# AudioAmp.net
KiCad netlist of a schematic drawn in Altium Designer
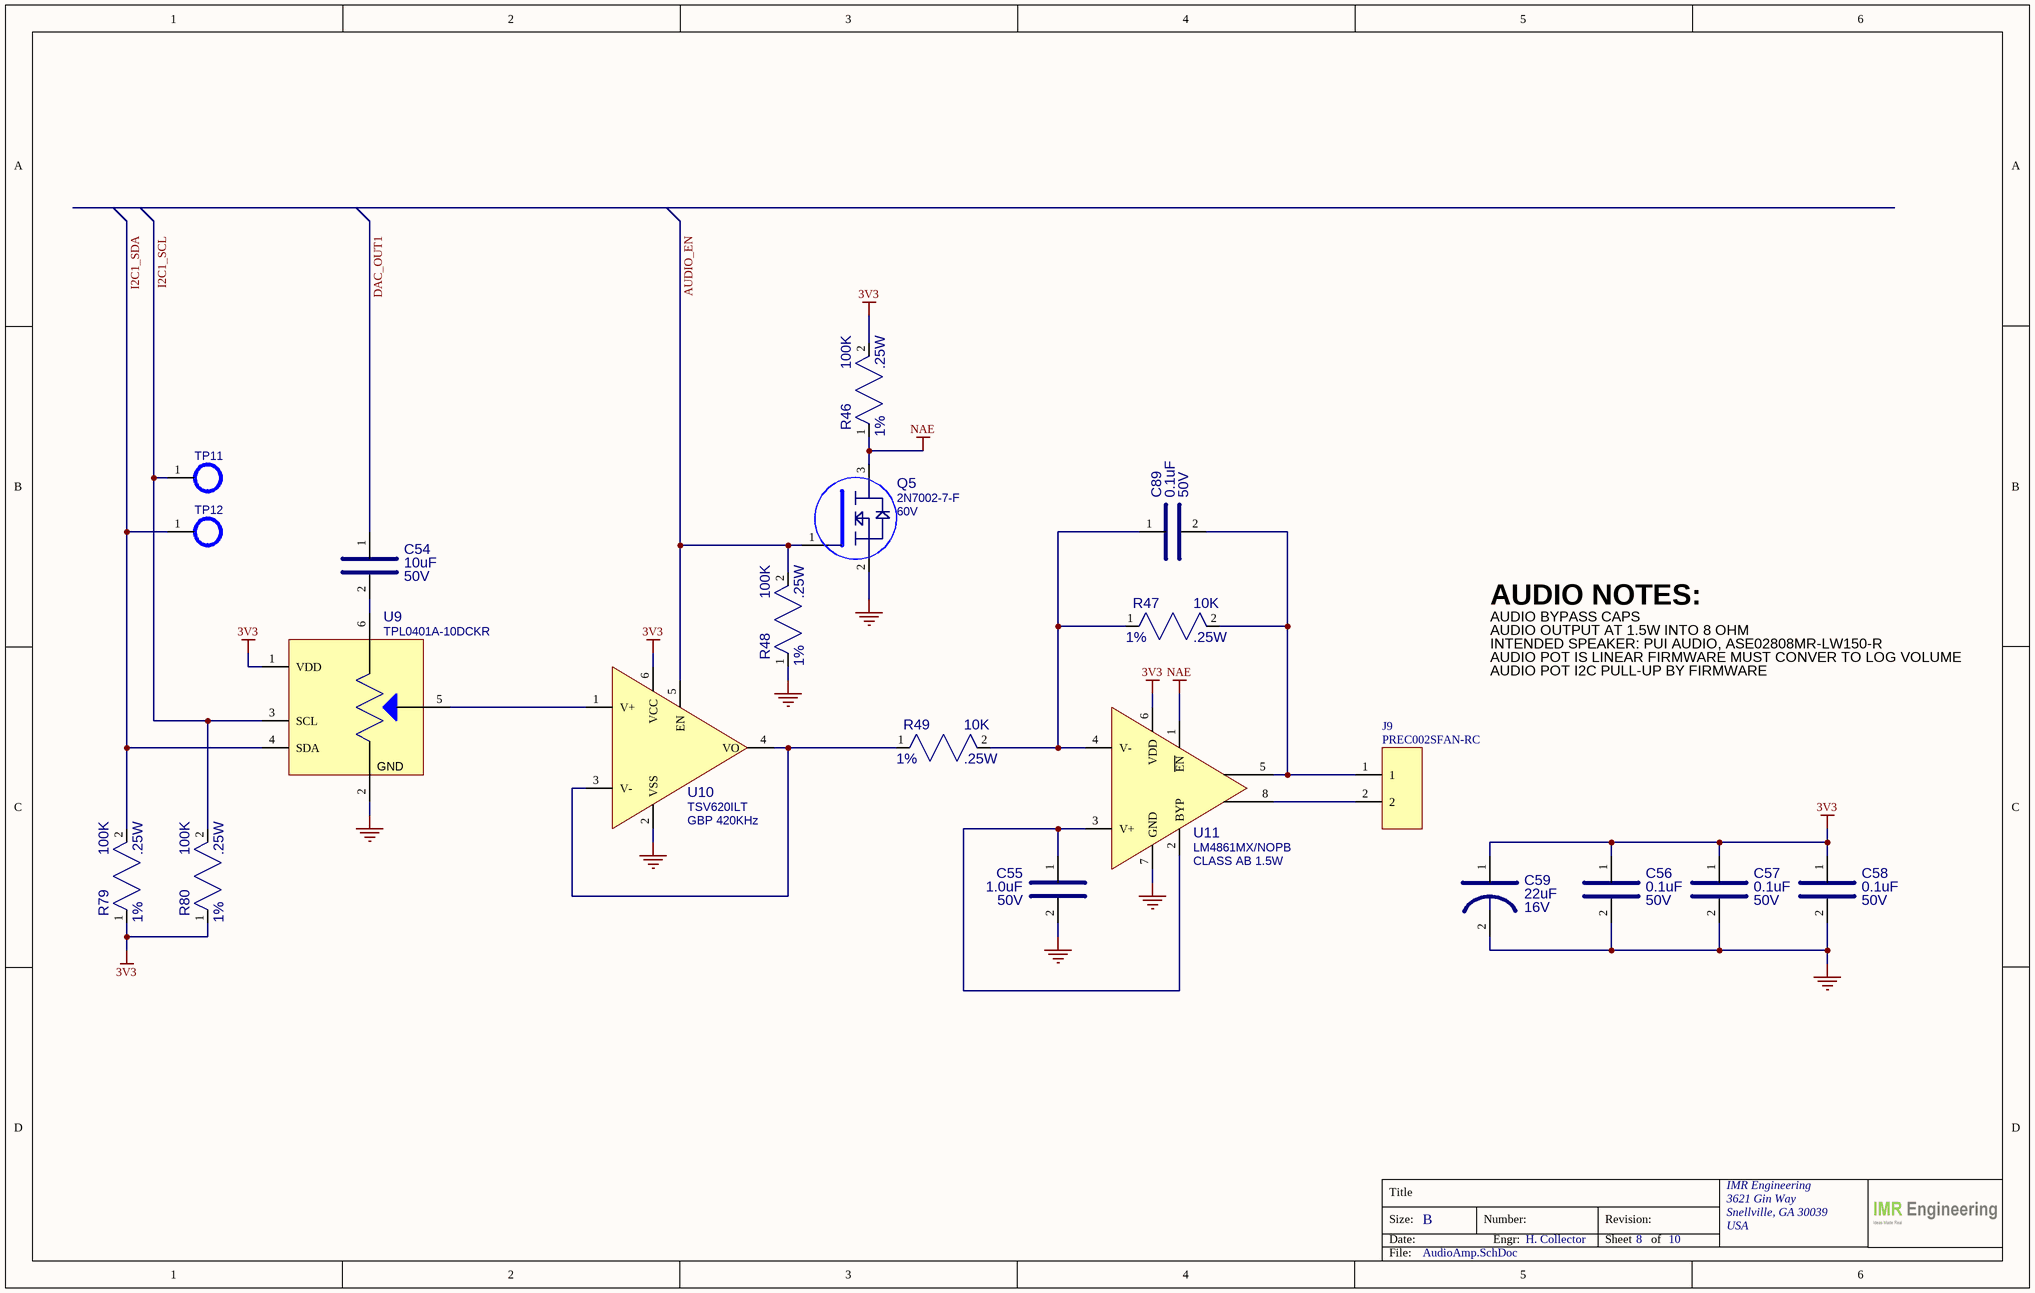
[diagram p0: AudioAmp.SchDoc]

(export (version "E")
  (design (tool "Eeschema 10.0.6"))
  (components
    (comp (ref "C54")
      (value "10uF")
      (footprint "CAP_1206")
      (description "CAP CER 10UF 50V X5R 1206")
      (fields
        (field (name "MFG") "Samsung Electro-Mechanics")
        (field (name "TOLERANCE") "10%")
        (field (name "VOLTAGE") "50V")
      )
      (libsource (lib "IMR_Lib") (part "CAP_10UF_50V_1206"))
    )
    (comp (ref "C55")
      (value "1.0uF")
      (footprint "CAP_0805")
      (description "CAP CER 1UF 50V X7R 0805")
      (fields
        (field (name "MFG") "Taiyo Yuden")
        (field (name "TOLERANCE") "20%")
        (field (name "VOLTAGE") "50V")
      )
      (libsource (lib "IMR_Lib") (part "CAP_1.0UF_50V_0805"))
    )
    (comp (ref "C56")
      (value "0.1uF")
      (footprint "CAP_0805")
      (description "CAP CER 0.1UF 50V X7R 0805")
      (fields (field (name "MFG") "AVX") (field (name "TOLERANCE") "10%") (field (name "VOLTAGE") "50V"))
      (libsource (lib "IMR_Lib") (part "CAP_0.1UF_50V_0805"))
    )
    (comp (ref "C57")
      (value "0.1uF")
      (footprint "CAP_0805")
      (description "CAP CER 0.1UF 50V X7R 0805")
      (fields (field (name "MFG") "AVX") (field (name "TOLERANCE") "10%") (field (name "VOLTAGE") "50V"))
      (libsource (lib "IMR_Lib") (part "CAP_0.1UF_50V_0805"))
    )
    (comp (ref "C58")
      (value "0.1uF")
      (footprint "CAP_0805")
      (description "CAP CER 0.1UF 50V X7R 0805")
      (fields (field (name "MFG") "AVX") (field (name "TOLERANCE") "10%") (field (name "VOLTAGE") "50V"))
      (libsource (lib "IMR_Lib") (part "CAP_0.1UF_50V_0805"))
    )
    (comp (ref "C59")
      (value "22uF")
      (footprint "CAP_2312")
      (description "CAP TANT 22UF 20% 16V 2312")
      (fields
        (field (name "MFG") "AVX Corporation")
        (field (name "TOLERANCE") "10%")
        (field (name "VOLTAGE") "16V")
      )
      (libsource (lib "IMR_Lib") (part "CAP_22UF_16V_TANT"))
    )
    (comp (ref "C89")
      (value "0.1uF")
      (footprint "CAP_0805")
      (description "CAP CER 0.1UF 50V X7R 0805")
      (fields (field (name "MFG") "AVX") (field (name "TOLERANCE") "10%") (field (name "VOLTAGE") "50V"))
      (libsource (lib "IMR_Lib") (part "CAP_0.1UF_50V_0805"))
    )
    (comp (ref "J9")
      (value "PREC002SFAN-RC")
      (footprint "HDR_1X2_100MILL")
      (description "CONN HEADER VERT 2POS 2.54MM")
      (fields (field (name "MFG") "Sullins Connector Solutions"))
      (libsource (lib "IMR_Lib") (part "CONN_2P_SINGLE_ROW"))
    )
    (comp (ref "Q5")
      (value "60V")
      (footprint "SOT-23")
      (description "MOSFET N-CH 60V 115MA SOT23-3")
      (fields
        (field (name "MFG") "Diodes Incorporated")
        (field (name "MFG_PN") "2N7002-7-F")
        (field (name "Comment") "2N7002-7-F")
      )
      (libsource (lib "IMR_Lib") (part "MOSFET_NCH_2N7002-7-F"))
    )
    (comp (ref "R46")
      (value "100K")
      (footprint "PMG_RES_0805")
      (description "RES SMD 100K OHM 1% 1/4W 0805")
      (fields
        (field (name "MFG") "KOA Speer Electronics, Inc.")
        (field (name "TOLERANCE") "1%")
        (field (name "POWER") ".25W")
        (field (name "Comment") "RK73H2ATTD1003F")
      )
      (libsource (lib "IMR_Lib") (part "RES_100K_0805_1/4W_1%"))
    )
    (comp (ref "R47")
      (value "10K")
      (footprint "RES_0805")
      (description "RES SMD 10K OHM 1% 1/4W 0805")
      (fields
        (field (name "MFG") "KOA Speer Electronics, Inc.")
        (field (name "TOLERANCE") "1%")
        (field (name "POWER") ".25W")
        (field (name "Comment") "SG73S2ATTD1002F")
      )
      (libsource (lib "IMR_Lib") (part "RES_10K_0805_1/4W_1%"))
    )
    (comp (ref "R48")
      (value "100K")
      (footprint "PMG_RES_0805")
      (description "RES SMD 100K OHM 1% 1/4W 0805")
      (fields
        (field (name "MFG") "KOA Speer Electronics, Inc.")
        (field (name "TOLERANCE") "1%")
        (field (name "POWER") ".25W")
        (field (name "Comment") "RK73H2ATTD1003F")
      )
      (libsource (lib "IMR_Lib") (part "RES_100K_0805_1/4W_1%"))
    )
    (comp (ref "R49")
      (value "10K")
      (footprint "RES_0805")
      (description "RES SMD 10K OHM 1% 1/4W 0805")
      (fields
        (field (name "MFG") "KOA Speer Electronics, Inc.")
        (field (name "TOLERANCE") "1%")
        (field (name "POWER") ".25W")
        (field (name "Comment") "SG73S2ATTD1002F")
      )
      (libsource (lib "IMR_Lib") (part "RES_10K_0805_1/4W_1%"))
    )
    (comp (ref "R79")
      (value "100K")
      (footprint "PMG_RES_0805")
      (description "RES SMD 100K OHM 1% 1/4W 0805")
      (fields
        (field (name "MFG") "KOA Speer Electronics, Inc.")
        (field (name "TOLERANCE") "1%")
        (field (name "POWER") ".25W")
        (field (name "Comment") "RK73H2ATTD1003F")
      )
      (libsource (lib "IMR_Lib") (part "RES_100K_0805_1/4W_1%"))
    )
    (comp (ref "R80")
      (value "100K")
      (footprint "PMG_RES_0805")
      (description "RES SMD 100K OHM 1% 1/4W 0805")
      (fields
        (field (name "MFG") "KOA Speer Electronics, Inc.")
        (field (name "TOLERANCE") "1%")
        (field (name "POWER") ".25W")
        (field (name "Comment") "RK73H2ATTD1003F")
      )
      (libsource (lib "IMR_Lib") (part "RES_100K_0805_1/4W_1%"))
    )
    (comp (ref "TP11")
      (value "TP_0635MM_HOLE")
      (footprint "TP_0635MM_HOLE")
      (description "3MM IN D. MT HOLE")
      (libsource (lib "IMR_Lib") (part "TP_0635MM_HOLE"))
    )
    (comp (ref "TP12")
      (value "TP_0635MM_HOLE")
      (footprint "TP_0635MM_HOLE")
      (description "3MM IN D. MT HOLE")
      (libsource (lib "IMR_Lib") (part "TP_0635MM_HOLE"))
    )
    (comp (ref "U9")
      (value "10K")
      (footprint "SOT-363_6-TSSOP_SC-88")
      (description "IC DGTL POT 10KOHM 128TAP SC70-6")
      (fields
        (field (name "MFG") "Texas Instruments")
        (field (name "MFG_PN") "TPL0401A-10DCKR")
        (field (name "TOLERANCE") "20%")
        (field (name "POWER") "5.5V")
        (field (name "Comment") "TPL0401A-10DCKR")
      )
      (libsource (lib "IMR_Lib") (part "IC_TPL0401A-10DCKR"))
    )
    (comp (ref "U10")
      (value "GBP 420KHz")
      (footprint "SOT23-6")
      (description "IC OPAMP GP 1 CIRCUIT SOT23-6")
      (fields
        (field (name "MFG") "STMicroelectronics")
        (field (name "MFG_PN") "TSV620ILT")
        (field (name "Comment") "TSV620ILT")
      )
      (libsource (lib "IMR_Lib") (part "IC_OPAMP_TSV620ILT"))
    )
    (comp (ref "U11")
      (value "CLASS AB 1.5W")
      (footprint "SO-8")
      (description "IC AMP CLASS AB MONO 1.5W 8SOIC")
      (fields
        (field (name "MFG") "Texas Instruments")
        (field (name "MFG_PN") "LM4861MX/NOPB")
        (field (name "Comment") "LM4861MX/NOPB")
      )
      (libsource (lib "IMR_Lib") (part "IC_OPAMP_LM4861"))
    )
  )
  (nets
    (net (code "1") (name "/AUDIO_EN") (class "Default")
      (node (ref "Q5") (pin "1") (pinfunction "B_1") (pintype "passive"))
      (node (ref "R48") (pin "2") (pinfunction "2_2") (pintype "passive"))
      (node (ref "U10") (pin "5") (pinfunction "EN_5") (pintype "passive"))
    )
    (net (code "2") (name "/DAC_OUT1") (class "Default")
      (node (ref "C54") (pin "1") (pinfunction "1_1") (pintype "passive"))
    )
    (net (code "3") (name "/I2C1_SCL") (class "Default")
      (node (ref "R80") (pin "2") (pinfunction "2_2") (pintype "passive"))
      (node (ref "TP11") (pin "1") (pinfunction "1_1") (pintype "passive"))
      (node (ref "U9") (pin "3") (pinfunction "SCL_3") (pintype "passive"))
    )
    (net (code "4") (name "/I2C1_SDA") (class "Default")
      (node (ref "R79") (pin "2") (pinfunction "2_2") (pintype "passive"))
      (node (ref "TP12") (pin "1") (pinfunction "1_1") (pintype "passive"))
      (node (ref "U9") (pin "4") (pinfunction "SDA_4") (pintype "passive"))
    )
    (net (code "5") (name "3V3") (class "Default")
      (node (ref "C56") (pin "1") (pinfunction "1_1") (pintype "passive"))
      (node (ref "C57") (pin "1") (pinfunction "1_1") (pintype "passive"))
      (node (ref "C58") (pin "1") (pinfunction "1_1") (pintype "passive"))
      (node (ref "C59") (pin "1") (pinfunction "1_1") (pintype "passive"))
      (node (ref "R46") (pin "2") (pinfunction "2_2") (pintype "passive"))
      (node (ref "R79") (pin "1") (pinfunction "1_1") (pintype "passive"))
      (node (ref "R80") (pin "1") (pinfunction "1_1") (pintype "passive"))
      (node (ref "U10") (pin "6") (pinfunction "VCC_6") (pintype "passive"))
      (node (ref "U11") (pin "6") (pinfunction "VDD_6") (pintype "passive"))
      (node (ref "U9") (pin "1") (pinfunction "VDD_1") (pintype "passive"))
    )
    (net (code "6") (name "GND") (class "Default")
      (node (ref "C55") (pin "2") (pinfunction "2_2") (pintype "passive"))
      (node (ref "C56") (pin "2") (pinfunction "2_2") (pintype "passive"))
      (node (ref "C57") (pin "2") (pinfunction "2_2") (pintype "passive"))
      (node (ref "C58") (pin "2") (pinfunction "2_2") (pintype "passive"))
      (node (ref "C59") (pin "2") (pinfunction "2_2") (pintype "passive"))
      (node (ref "Q5") (pin "2") (pinfunction "E_2") (pintype "passive"))
      (node (ref "R48") (pin "1") (pinfunction "1_1") (pintype "passive"))
      (node (ref "U10") (pin "2") (pinfunction "VSS_2") (pintype "passive"))
      (node (ref "U11") (pin "7") (pinfunction "GND_7") (pintype "passive"))
      (node (ref "U9") (pin "2") (pinfunction "GND_2") (pintype "passive"))
    )
    (net (code "7") (name "NAE") (class "Default")
      (node (ref "Q5") (pin "3") (pinfunction "C_3") (pintype "passive"))
      (node (ref "R46") (pin "1") (pinfunction "1_1") (pintype "passive"))
      (node (ref "U11") (pin "1") (pinfunction "EN_1") (pintype "passive"))
    )
    (net (code "8") (name "Net-(U9-H)") (class "Default")
      (node (ref "C54") (pin "2") (pinfunction "2_2") (pintype "passive"))
      (node (ref "U9") (pin "6") (pinfunction "H_6") (pintype "passive"))
    )
    (net (code "9") (name "Net-(U10-V+)") (class "Default")
      (node (ref "U10") (pin "1") (pinfunction "V+_1") (pintype "passive"))
      (node (ref "U9") (pin "5") (pinfunction "W_5") (pintype "passive"))
    )
    (net (code "10") (name "Net-(U10-V-)") (class "Default")
      (node (ref "R49") (pin "1") (pinfunction "1_1") (pintype "passive"))
      (node (ref "U10") (pin "3") (pinfunction "V-_3") (pintype "passive"))
      (node (ref "U10") (pin "4") (pinfunction "VO_4") (pintype "passive"))
    )
    (net (code "11") (name "Net-(U11-BYP)") (class "Default")
      (node (ref "C55") (pin "1") (pinfunction "1_1") (pintype "passive"))
      (node (ref "U11") (pin "2") (pinfunction "BYP_2") (pintype "passive"))
      (node (ref "U11") (pin "3") (pinfunction "V+_3") (pintype "passive"))
    )
    (net (code "12") (name "Net-(U11-V-)") (class "Default")
      (node (ref "C89") (pin "1") (pinfunction "1_1") (pintype "passive"))
      (node (ref "R47") (pin "1") (pinfunction "1_1") (pintype "passive"))
      (node (ref "R49") (pin "2") (pinfunction "2_2") (pintype "passive"))
      (node (ref "U11") (pin "4") (pinfunction "V-_4") (pintype "passive"))
    )
    (net (code "13") (name "Net-(U11-VO1)") (class "Default")
      (node (ref "C89") (pin "2") (pinfunction "2_2") (pintype "passive"))
      (node (ref "J9") (pin "1") (pinfunction "1_1") (pintype "passive"))
      (node (ref "R47") (pin "2") (pinfunction "2_2") (pintype "passive"))
      (node (ref "U11") (pin "5") (pinfunction "VO1_5") (pintype "passive"))
    )
    (net (code "14") (name "Net-(U11-VO2)") (class "Default")
      (node (ref "J9") (pin "2") (pinfunction "2_2") (pintype "passive"))
      (node (ref "U11") (pin "8") (pinfunction "VO2_8") (pintype "passive"))
    )
  )
)
